# Sheet1.net
KiCad netlist of a schematic drawn in Altium Designer
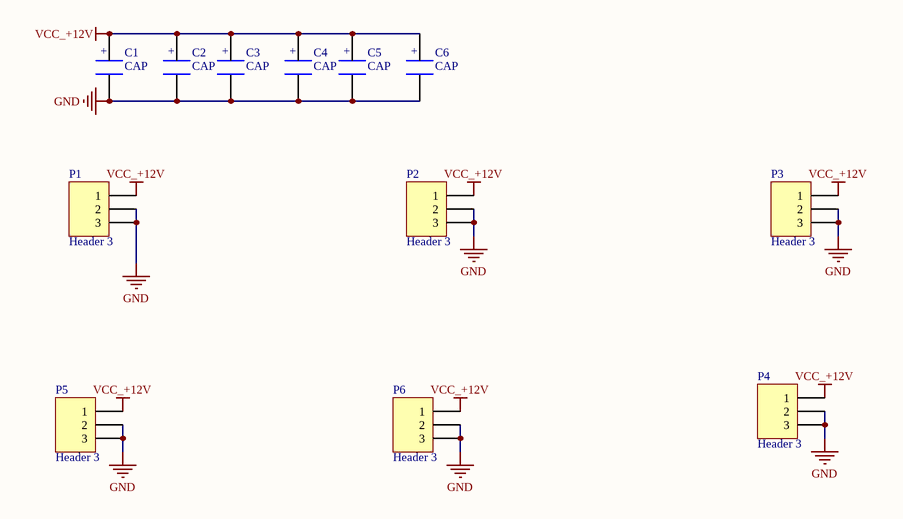
[diagram p0: Sheet1.SchDoc]

(export (version "E")
  (design (tool "Eeschema 10.0.6"))
  (components
    (comp (ref "C1") (value "CAP") (footprint "8X12_CAP") (libsource (lib "mylib") (part "CAP")))
    (comp (ref "C2") (value "CAP") (footprint "8X12_CAP") (libsource (lib "mylib") (part "CAP")))
    (comp (ref "C3") (value "CAP") (footprint "8X12_CAP") (libsource (lib "mylib") (part "CAP")))
    (comp (ref "C4") (value "CAP") (footprint "8X12_CAP") (libsource (lib "mylib") (part "CAP")))
    (comp (ref "C5") (value "CAP") (footprint "8X12_CAP") (libsource (lib "mylib") (part "CAP")))
    (comp (ref "C6") (value "CAP") (footprint "8X12_CAP") (libsource (lib "mylib") (part "CAP")))
    (comp (ref "P1")
      (value "Header 3")
      (footprint "DC-005")
      (description "Header, 3-Pin")
      (fields (field (name "PUBLISHER") "Altium Limited"))
      (libsource (lib "Miscellaneous Connectors") (part "Header 3"))
    )
    (comp (ref "P2")
      (value "Header 3")
      (footprint "DC-005")
      (description "Header, 3-Pin")
      (fields (field (name "PUBLISHER") "Altium Limited"))
      (libsource (lib "Miscellaneous Connectors") (part "Header 3"))
    )
    (comp (ref "P3")
      (value "Header 3")
      (footprint "DC-005")
      (description "Header, 3-Pin")
      (fields (field (name "PUBLISHER") "Altium Limited"))
      (libsource (lib "Miscellaneous Connectors") (part "Header 3"))
    )
    (comp (ref "P4")
      (value "Header 3")
      (footprint "DC-005")
      (description "Header, 3-Pin")
      (fields (field (name "PUBLISHER") "Altium Limited"))
      (libsource (lib "Miscellaneous Connectors") (part "Header 3"))
    )
    (comp (ref "P5")
      (value "Header 3")
      (footprint "DC-005")
      (description "Header, 3-Pin")
      (fields (field (name "PUBLISHER") "Altium Limited"))
      (libsource (lib "Miscellaneous Connectors") (part "Header 3"))
    )
    (comp (ref "P6")
      (value "Header 3")
      (footprint "DC-005")
      (description "Header, 3-Pin")
      (fields (field (name "PUBLISHER") "Altium Limited"))
      (libsource (lib "Miscellaneous Connectors") (part "Header 3"))
    )
  )
  (nets
    (net (code "1") (name "GND") (class "Default")
      (node (ref "C1") (pin "2") (pinfunction "2_2") (pintype "passive"))
      (node (ref "C2") (pin "2") (pinfunction "2_2") (pintype "passive"))
      (node (ref "C3") (pin "2") (pinfunction "2_2") (pintype "passive"))
      (node (ref "C4") (pin "2") (pinfunction "2_2") (pintype "passive"))
      (node (ref "C5") (pin "2") (pinfunction "2_2") (pintype "passive"))
      (node (ref "C6") (pin "2") (pinfunction "2_2") (pintype "passive"))
      (node (ref "P1") (pin "2") (pinfunction "2_2") (pintype "passive"))
      (node (ref "P1") (pin "3") (pinfunction "3_3") (pintype "passive"))
      (node (ref "P2") (pin "2") (pinfunction "2_2") (pintype "passive"))
      (node (ref "P2") (pin "3") (pinfunction "3_3") (pintype "passive"))
      (node (ref "P3") (pin "2") (pinfunction "2_2") (pintype "passive"))
      (node (ref "P3") (pin "3") (pinfunction "3_3") (pintype "passive"))
      (node (ref "P4") (pin "2") (pinfunction "2_2") (pintype "passive"))
      (node (ref "P4") (pin "3") (pinfunction "3_3") (pintype "passive"))
      (node (ref "P5") (pin "2") (pinfunction "2_2") (pintype "passive"))
      (node (ref "P5") (pin "3") (pinfunction "3_3") (pintype "passive"))
      (node (ref "P6") (pin "2") (pinfunction "2_2") (pintype "passive"))
      (node (ref "P6") (pin "3") (pinfunction "3_3") (pintype "passive"))
    )
    (net (code "2") (name "VCC_+12V") (class "Default")
      (node (ref "C1") (pin "1") (pinfunction "1_1") (pintype "passive"))
      (node (ref "C2") (pin "1") (pinfunction "1_1") (pintype "passive"))
      (node (ref "C3") (pin "1") (pinfunction "1_1") (pintype "passive"))
      (node (ref "C4") (pin "1") (pinfunction "1_1") (pintype "passive"))
      (node (ref "C5") (pin "1") (pinfunction "1_1") (pintype "passive"))
      (node (ref "C6") (pin "1") (pinfunction "1_1") (pintype "passive"))
      (node (ref "P1") (pin "1") (pinfunction "1_1") (pintype "passive"))
      (node (ref "P2") (pin "1") (pinfunction "1_1") (pintype "passive"))
      (node (ref "P3") (pin "1") (pinfunction "1_1") (pintype "passive"))
      (node (ref "P4") (pin "1") (pinfunction "1_1") (pintype "passive"))
      (node (ref "P5") (pin "1") (pinfunction "1_1") (pintype "passive"))
      (node (ref "P6") (pin "1") (pinfunction "1_1") (pintype "passive"))
    )
  )
)
